# S01-17676.net
KiCad netlist of a schematic drawn in Altium Designer
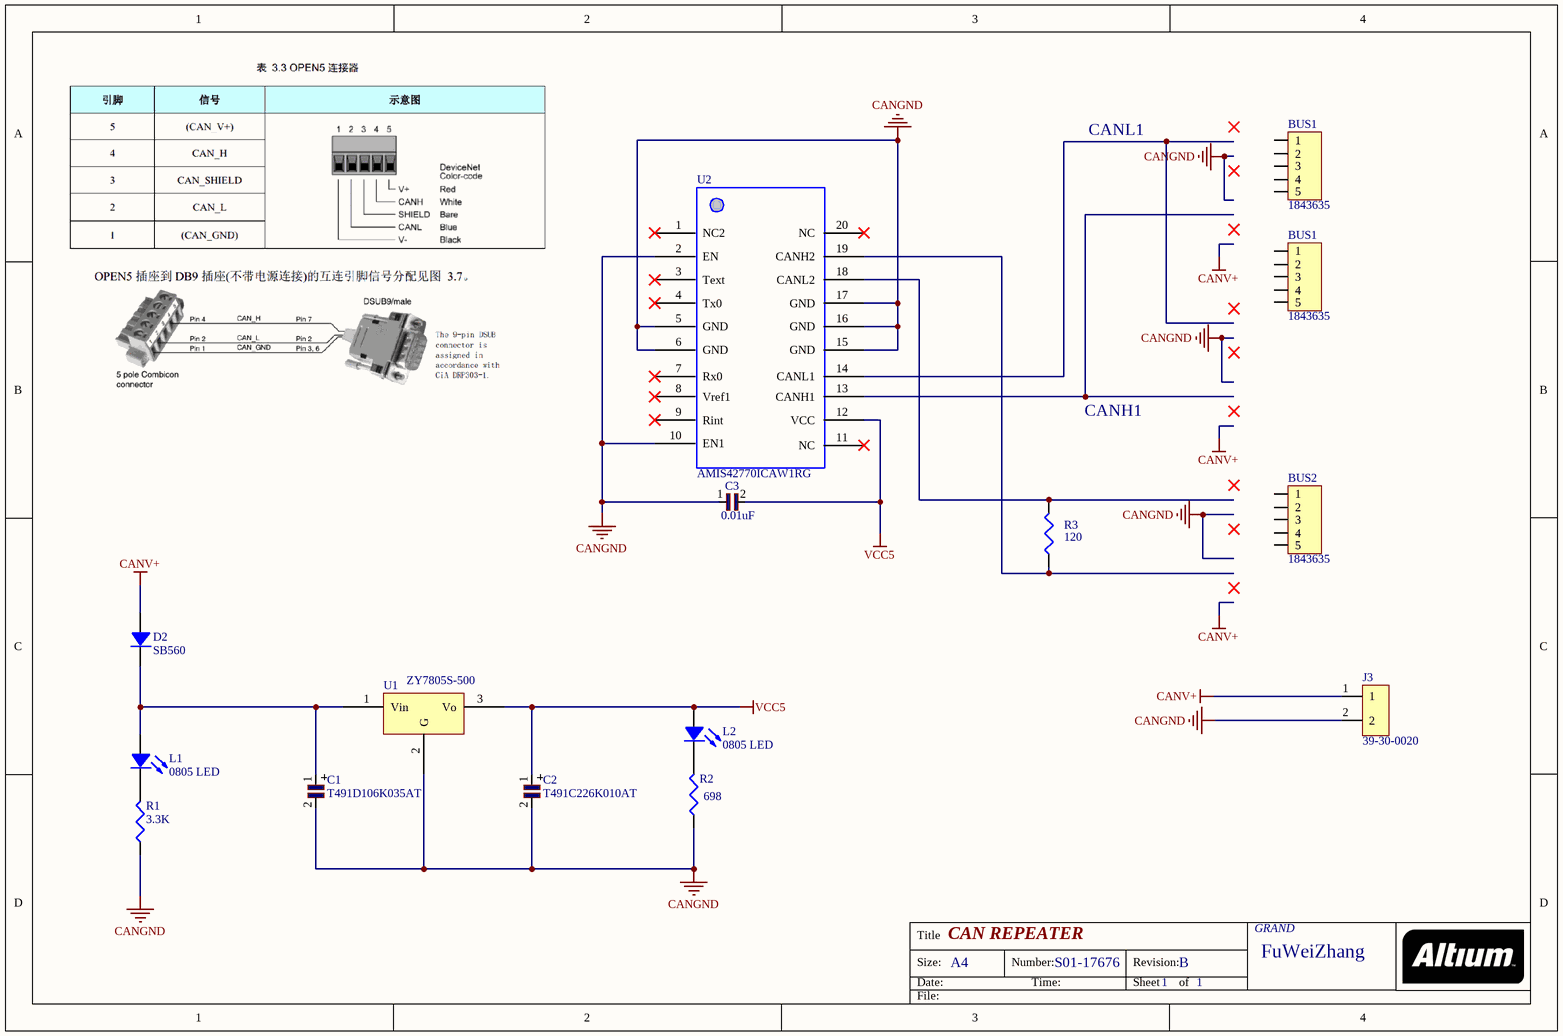
[diagram p0: S01-17676.SchDoc]

(export (version "E")
  (design (tool "Eeschema 10.0.6"))
  (components
    (comp (ref "BUS1")
      (value "1843635")
      (footprint "1843635")
      (description "端子块, 针座, 3.5 mm, 5 路, 8 A, 160 V, 通孔竖直")
      (libsource (lib "FUWEIZHANG") (part "1843635"))
    )
    (comp (ref "BUS2")
      (value "1843635")
      (footprint "1843635")
      (description "端子块, 针座, 3.5 mm, 5 路, 8 A, 160 V, 通孔竖直")
      (libsource (lib "FUWEIZHANG") (part "1843635"))
    )
    (comp (ref "C1")
      (value "T491D106K035AT")
      (footprint "T491D106K035AT")
      (description "表面贴装钽电容, 10 μF, 35 V, T491 系列, ± 10%, 2917 [7343 公制]")
      (libsource (lib "FUWEIZHANG") (part "T491D106K035AT"))
    )
    (comp (ref "C2")
      (value "T491C226K010AT")
      (footprint "T491C226K010AT")
      (description "表面贴装钽电容, 22 μF, 10 V, T491 系列, ± 10%, 2312 [6032 公")
      (libsource (lib "FUWEIZHANG") (part "T491C226K010AT"))
    )
    (comp (ref "C3")
      (value "0.01uF")
      (footprint "0805 Capacitor")
      (libsource (lib "FUWEIZHANG") (part "0805 Capacitor"))
    )
    (comp (ref "D2")
      (value "SB560")
      (footprint "SB560")
      (description "肖特基二极管与整流器 5a/60V")
      (libsource (lib "FUWEIZHANG") (part "SB560"))
    )
    (comp (ref "J3")
      (value "39-30-0020")
      (footprint "39-30-0020")
      (description "线至板连接器, 4.2 mm, 2 触点, 针座, Mini-Fit Jr. 5569系列, 通孔安装")
      (libsource (lib "FUWEIZHANG") (part "39-30-0020"))
    )
    (comp (ref "L1")
      (value "0805 LED")
      (footprint "0805 LED")
      (libsource (lib "FUWEIZHANG") (part "0805 LED"))
    )
    (comp (ref "L2")
      (value "0805 LED")
      (footprint "0805 LED")
      (libsource (lib "FUWEIZHANG") (part "0805 LED"))
    )
    (comp (ref "R1")
      (value "3.3K")
      (footprint "0805 Resistor")
      (libsource (lib "FUWEIZHANG") (part "0805 Resistor"))
    )
    (comp (ref "R2")
      (value "698")
      (footprint "0805 Resistor")
      (libsource (lib "FUWEIZHANG") (part "0805 Resistor"))
    )
    (comp (ref "R3")
      (value "120")
      (footprint "0805 Resistor")
      (libsource (lib "FUWEIZHANG") (part "0805 Resistor"))
    )
    (comp (ref "U1")
      (value "ZY7805S-500")
      (footprint "ZY78xxS-500")
      (libsource (lib "ZY-power") (part "ZY78xxS-500"))
    )
    (comp (ref "U2")
      (value "AMIS42770ICAW1RG")
      (footprint "AMIS42770ICAW1RG")
      (description "CAN REPEATER")
      (libsource (lib "FUWEIZHANG") (part "AMIS42770ICAW1RG"))
    )
  )
  (nets
    (net (code "1") (name "CANGND") (class "Default")
      (node (ref "C1") (pin "2") (pinfunction "2_2") (pintype "passive"))
      (node (ref "C2") (pin "2") (pinfunction "2_2") (pintype "passive"))
      (node (ref "C3") (pin "1") (pinfunction "1_1") (pintype "passive"))
      (node (ref "J3") (pin "2") (pinfunction "2_2") (pintype "passive"))
      (node (ref "R1") (pin "1") (pinfunction "1_1") (pintype "passive"))
      (node (ref "R2") (pin "1") (pinfunction "1_1") (pintype "passive"))
      (node (ref "U1") (pin "2") (pinfunction "G_2") (pintype "passive"))
      (node (ref "U2") (pin "10") (pinfunction "EN1_10") (pintype "passive"))
      (node (ref "U2") (pin "15") (pinfunction "GND_15") (pintype "passive"))
      (node (ref "U2") (pin "16") (pinfunction "GND_16") (pintype "passive"))
      (node (ref "U2") (pin "17") (pinfunction "GND_17") (pintype "passive"))
      (node (ref "U2") (pin "2") (pinfunction "EN_2") (pintype "passive"))
      (node (ref "U2") (pin "5") (pinfunction "GND_5") (pintype "passive"))
      (node (ref "U2") (pin "6") (pinfunction "GND_6") (pintype "passive"))
    )
    (net (code "2") (name "CANV+") (class "Default")
      (node (ref "D2") (pin "1") (pinfunction "1_1") (pintype "passive"))
      (node (ref "J3") (pin "1") (pinfunction "1_1") (pintype "passive"))
    )
    (net (code "3") (name "Net-(L1-A)") (class "Default")
      (node (ref "C1") (pin "1") (pinfunction "1_1") (pintype "passive"))
      (node (ref "D2") (pin "2") (pinfunction "2_2") (pintype "passive"))
      (node (ref "L1") (pin "1") (pinfunction "A_1") (pintype "passive"))
      (node (ref "U1") (pin "1") (pinfunction "Vin_1") (pintype "passive"))
    )
    (net (code "4") (name "Net-(L1-K)") (class "Default")
      (node (ref "L1") (pin "2") (pinfunction "K_2") (pintype "passive"))
      (node (ref "R1") (pin "2") (pinfunction "2_2") (pintype "passive"))
    )
    (net (code "5") (name "Net-(L2-K)") (class "Default")
      (node (ref "L2") (pin "2") (pinfunction "K_2") (pintype "passive"))
      (node (ref "R2") (pin "2") (pinfunction "2_2") (pintype "passive"))
    )
    (net (code "6") (name "Net-(U2-CANH2)") (class "Default")
      (node (ref "R3") (pin "1") (pinfunction "1_1") (pintype "passive"))
      (node (ref "U2") (pin "19") (pinfunction "CANH2_19") (pintype "passive"))
    )
    (net (code "7") (name "Net-(U2-CANL2)") (class "Default")
      (node (ref "R3") (pin "2") (pinfunction "2_2") (pintype "passive"))
      (node (ref "U2") (pin "18") (pinfunction "CANL2_18") (pintype "passive"))
    )
    (net (code "8") (name "VCC5") (class "Default")
      (node (ref "C2") (pin "1") (pinfunction "1_1") (pintype "passive"))
      (node (ref "C3") (pin "2") (pinfunction "2_2") (pintype "passive"))
      (node (ref "L2") (pin "1") (pinfunction "A_1") (pintype "passive"))
      (node (ref "U1") (pin "3") (pinfunction "Vo_3") (pintype "passive"))
      (node (ref "U2") (pin "12") (pinfunction "VCC_12") (pintype "passive"))
    )
    (net (code "9") (name "unconnected-(BUS1-Pad1)") (class "Default")
      (node (ref "BUS1") (pin "1") (pinfunction "1_1") (pintype "passive"))
    )
    (net (code "10") (name "unconnected-(BUS1-Pad1)_1") (class "Default")
      (node (ref "BUS1") (pin "1") (pinfunction "1_1") (pintype "passive"))
    )
    (net (code "11") (name "unconnected-(BUS1-Pad2)") (class "Default")
      (node (ref "BUS1") (pin "2") (pinfunction "2_2") (pintype "passive"))
    )
    (net (code "12") (name "unconnected-(BUS1-Pad2)_1") (class "Default")
      (node (ref "BUS1") (pin "2") (pinfunction "2_2") (pintype "passive"))
    )
    (net (code "13") (name "unconnected-(BUS1-Pad3)") (class "Default")
      (node (ref "BUS1") (pin "3") (pinfunction "3_3") (pintype "passive"))
    )
    (net (code "14") (name "unconnected-(BUS1-Pad3)_1") (class "Default")
      (node (ref "BUS1") (pin "3") (pinfunction "3_3") (pintype "passive"))
    )
    (net (code "15") (name "unconnected-(BUS1-Pad4)") (class "Default")
      (node (ref "BUS1") (pin "4") (pinfunction "4_4") (pintype "passive"))
    )
    (net (code "16") (name "unconnected-(BUS1-Pad4)_1") (class "Default")
      (node (ref "BUS1") (pin "4") (pinfunction "4_4") (pintype "passive"))
    )
    (net (code "17") (name "unconnected-(BUS1-Pad5)") (class "Default")
      (node (ref "BUS1") (pin "5") (pinfunction "5_5") (pintype "passive"))
    )
    (net (code "18") (name "unconnected-(BUS1-Pad5)_1") (class "Default")
      (node (ref "BUS1") (pin "5") (pinfunction "5_5") (pintype "passive"))
    )
    (net (code "19") (name "unconnected-(BUS2-Pad1)") (class "Default")
      (node (ref "BUS2") (pin "1") (pinfunction "1_1") (pintype "passive"))
    )
    (net (code "20") (name "unconnected-(BUS2-Pad2)") (class "Default")
      (node (ref "BUS2") (pin "2") (pinfunction "2_2") (pintype "passive"))
    )
    (net (code "21") (name "unconnected-(BUS2-Pad3)") (class "Default")
      (node (ref "BUS2") (pin "3") (pinfunction "3_3") (pintype "passive"))
    )
    (net (code "22") (name "unconnected-(BUS2-Pad4)") (class "Default")
      (node (ref "BUS2") (pin "4") (pinfunction "4_4") (pintype "passive"))
    )
    (net (code "23") (name "unconnected-(BUS2-Pad5)") (class "Default")
      (node (ref "BUS2") (pin "5") (pinfunction "5_5") (pintype "passive"))
    )
    (net (code "24") (name "unconnected-(U2-CANH1-Pad13)") (class "Default")
      (node (ref "U2") (pin "13") (pinfunction "CANH1_13") (pintype "passive"))
    )
    (net (code "25") (name "unconnected-(U2-CANL1-Pad14)") (class "Default")
      (node (ref "U2") (pin "14") (pinfunction "CANL1_14") (pintype "passive"))
    )
    (net (code "26") (name "unconnected-(U2-NC-Pad11)") (class "Default")
      (node (ref "U2") (pin "11") (pinfunction "NC_11") (pintype "passive+no_connect"))
    )
    (net (code "27") (name "unconnected-(U2-NC-Pad20)") (class "Default")
      (node (ref "U2") (pin "20") (pinfunction "NC_20") (pintype "passive+no_connect"))
    )
    (net (code "28") (name "unconnected-(U2-NC2-Pad1)") (class "Default")
      (node (ref "U2") (pin "1") (pinfunction "NC2_1") (pintype "passive+no_connect"))
    )
    (net (code "29") (name "unconnected-(U2-Rint-Pad9)") (class "Default")
      (node (ref "U2") (pin "9") (pinfunction "Rint_9") (pintype "passive+no_connect"))
    )
    (net (code "30") (name "unconnected-(U2-Rx0-Pad7)") (class "Default")
      (node (ref "U2") (pin "7") (pinfunction "Rx0_7") (pintype "passive+no_connect"))
    )
    (net (code "31") (name "unconnected-(U2-Text-Pad3)") (class "Default")
      (node (ref "U2") (pin "3") (pinfunction "Text_3") (pintype "passive+no_connect"))
    )
    (net (code "32") (name "unconnected-(U2-Tx0-Pad4)") (class "Default")
      (node (ref "U2") (pin "4") (pinfunction "Tx0_4") (pintype "passive+no_connect"))
    )
    (net (code "33") (name "unconnected-(U2-Vref1-Pad8)") (class "Default")
      (node (ref "U2") (pin "8") (pinfunction "Vref1_8") (pintype "passive+no_connect"))
    )
  )
)
